# knife1.net
KiCad netlist of a schematic drawn in EAGLE
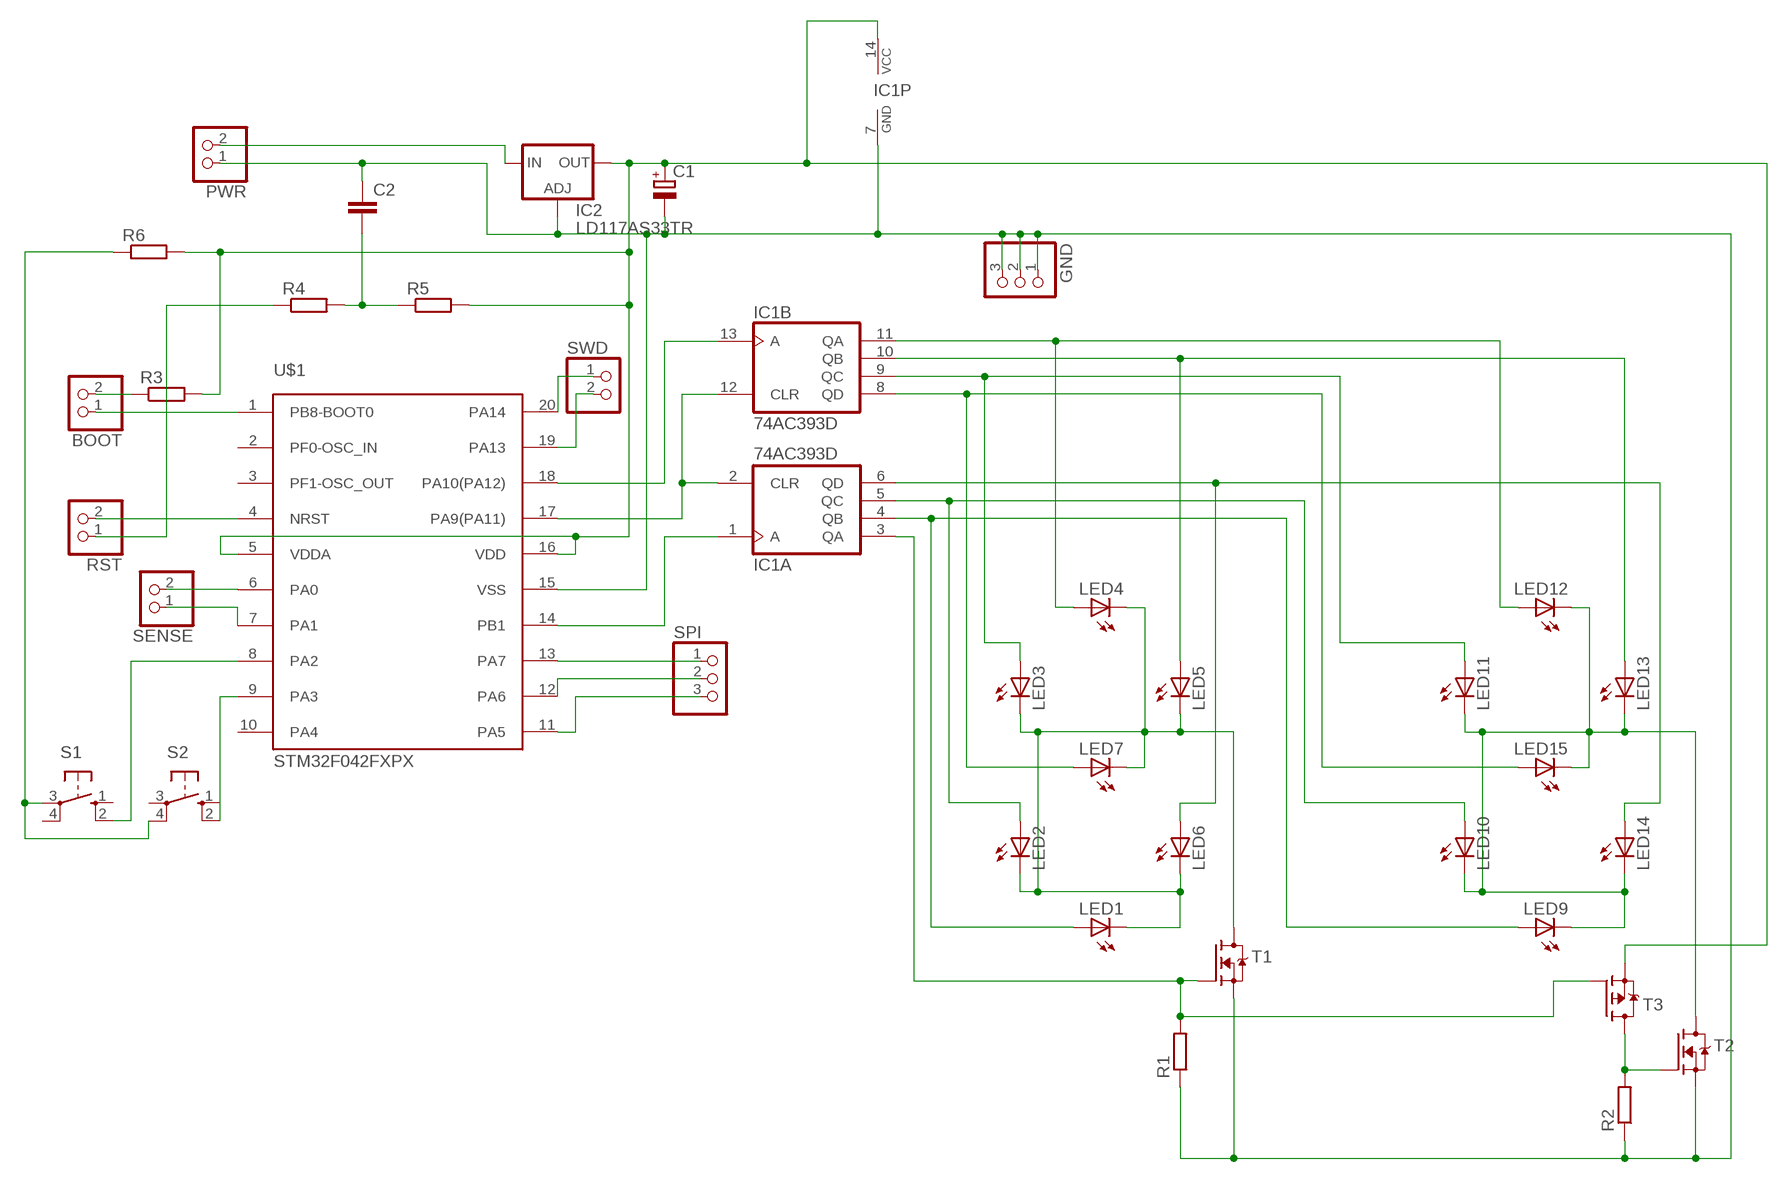
[diagram p0: schematic, sheet 1]

(export (version "E")
  (design (tool "Eeschema 10.0.6"))
  (components
    (comp (ref "BOOT")
      (value "PINHD-1X2")
      (footprint "eagle-import:1X02")
      (libsource (lib "eagle-import") (part "PINHD-1X2"))
    )
    (comp (ref "C1")
      (value "CPOL-EUSMCD")
      (footprint "eagle-import:SMC_D")
      (libsource (lib "eagle-import") (part "CPOL-EUSMCD"))
    )
    (comp (ref "C2")
      (value "C-EUC1206")
      (footprint "eagle-import:C1206")
      (libsource (lib "eagle-import") (part "C-EUC1206"))
    )
    (comp (ref "GND")
      (value "PINHD-1X3")
      (footprint "eagle-import:1X03")
      (libsource (lib "eagle-import") (part "PINHD-1X3"))
    )
    (comp (ref "IC1")
      (value "74AC393D")
      (footprint "eagle-import:SO14")
      (libsource (lib "eagle-import") (part "74393DAC"))
    )
    (comp (ref "IC2")
      (value "LD117AS33TR")
      (footprint "eagle-import:SOT223")
      (libsource (lib "eagle-import") (part "LD117A?S33TR"))
    )
    (comp (ref "LED1")
      (value "LEDSQR2X5")
      (footprint "eagle-import:LED2X5")
      (libsource (lib "eagle-import") (part "LEDSQR2X5"))
    )
    (comp (ref "LED2")
      (value "LEDSQR2X5")
      (footprint "eagle-import:LED2X5")
      (libsource (lib "eagle-import") (part "LEDSQR2X5"))
    )
    (comp (ref "LED3")
      (value "LEDSQR2X5")
      (footprint "eagle-import:LED2X5")
      (libsource (lib "eagle-import") (part "LEDSQR2X5"))
    )
    (comp (ref "LED4")
      (value "LEDSQR2X5")
      (footprint "eagle-import:LED2X5")
      (libsource (lib "eagle-import") (part "LEDSQR2X5"))
    )
    (comp (ref "LED5")
      (value "LEDSQR2X5")
      (footprint "eagle-import:LED2X5")
      (libsource (lib "eagle-import") (part "LEDSQR2X5"))
    )
    (comp (ref "LED6")
      (value "LEDSQR2X5")
      (footprint "eagle-import:LED2X5")
      (libsource (lib "eagle-import") (part "LEDSQR2X5"))
    )
    (comp (ref "LED7")
      (value "LEDSQR2X5")
      (footprint "eagle-import:LED2X5")
      (libsource (lib "eagle-import") (part "LEDSQR2X5"))
    )
    (comp (ref "LED9")
      (value "LEDSQR2X5")
      (footprint "eagle-import:LED2X5")
      (libsource (lib "eagle-import") (part "LEDSQR2X5"))
    )
    (comp (ref "LED10")
      (value "LEDSQR2X5")
      (footprint "eagle-import:LED2X5")
      (libsource (lib "eagle-import") (part "LEDSQR2X5"))
    )
    (comp (ref "LED11")
      (value "LEDSQR2X5")
      (footprint "eagle-import:LED2X5")
      (libsource (lib "eagle-import") (part "LEDSQR2X5"))
    )
    (comp (ref "LED12")
      (value "LEDSQR2X5")
      (footprint "eagle-import:LED2X5")
      (libsource (lib "eagle-import") (part "LEDSQR2X5"))
    )
    (comp (ref "LED13")
      (value "LEDSQR2X5")
      (footprint "eagle-import:LED2X5")
      (libsource (lib "eagle-import") (part "LEDSQR2X5"))
    )
    (comp (ref "LED14")
      (value "LEDSQR2X5")
      (footprint "eagle-import:LED2X5")
      (libsource (lib "eagle-import") (part "LEDSQR2X5"))
    )
    (comp (ref "LED15")
      (value "LEDSQR2X5")
      (footprint "eagle-import:LED2X5")
      (libsource (lib "eagle-import") (part "LEDSQR2X5"))
    )
    (comp (ref "PWR")
      (value "PINHD-1X2")
      (footprint "eagle-import:1X02")
      (libsource (lib "eagle-import") (part "PINHD-1X2"))
    )
    (comp (ref "R1")
      (value "R-EU_M1206")
      (footprint "eagle-import:M1206")
      (libsource (lib "eagle-import") (part "R-EU_M1206"))
    )
    (comp (ref "R2")
      (value "R-EU_M1206")
      (footprint "eagle-import:M1206")
      (libsource (lib "eagle-import") (part "R-EU_M1206"))
    )
    (comp (ref "R3")
      (value "R-EU_M1206")
      (footprint "eagle-import:M1206")
      (libsource (lib "eagle-import") (part "R-EU_M1206"))
    )
    (comp (ref "R4")
      (value "R-EU_M1206")
      (footprint "eagle-import:M1206")
      (libsource (lib "eagle-import") (part "R-EU_M1206"))
    )
    (comp (ref "R5")
      (value "R-EU_M1206")
      (footprint "eagle-import:M1206")
      (libsource (lib "eagle-import") (part "R-EU_M1206"))
    )
    (comp (ref "R6")
      (value "R-EU_M1206")
      (footprint "eagle-import:M1206")
      (libsource (lib "eagle-import") (part "R-EU_M1206"))
    )
    (comp (ref "RST")
      (value "PINHD-1X2")
      (footprint "eagle-import:1X02")
      (libsource (lib "eagle-import") (part "PINHD-1X2"))
    )
    (comp (ref "S1")
      (value "10-XX")
      (footprint "eagle-import:B3F-10XX")
      (fields (field (name "MPN") "B3F-1000"))
      (libsource (lib "eagle-import") (part "10-XX"))
    )
    (comp (ref "S2")
      (value "10-XX")
      (footprint "eagle-import:B3F-10XX")
      (fields (field (name "MPN") "B3F-1000"))
      (libsource (lib "eagle-import") (part "10-XX"))
    )
    (comp (ref "SENSE")
      (value "PINHD-1X2")
      (footprint "eagle-import:1X02")
      (libsource (lib "eagle-import") (part "PINHD-1X2"))
    )
    (comp (ref "SPI")
      (value "PINHD-1X3")
      (footprint "eagle-import:1X03")
      (libsource (lib "eagle-import") (part "PINHD-1X3"))
    )
    (comp (ref "SWD")
      (value "PINHD-1X2")
      (footprint "eagle-import:1X02")
      (libsource (lib "eagle-import") (part "PINHD-1X2"))
    )
    (comp (ref "T1")
      (value "MOSFET-N-SOT23")
      (footprint "eagle-import:SOT23")
      (libsource (lib "eagle-import") (part "MOSFET-N-SOT23"))
    )
    (comp (ref "T2")
      (value "MOSFET-N-SOT23")
      (footprint "eagle-import:SOT23")
      (libsource (lib "eagle-import") (part "MOSFET-N-SOT23"))
    )
    (comp (ref "T3")
      (value "MOSFET-P-SOT23")
      (footprint "eagle-import:SOT23")
      (libsource (lib "eagle-import") (part "MOSFET-P-SOT23"))
    )
    (comp (ref "U$1")
      (value "STM32F042FXPX")
      (footprint "eagle-import:TSSOP20")
      (libsource (lib "eagle-import") (part "STM32F042FXPX"))
    )
  )
  (nets
    (net (code "1") (name "Net-(BOOT-Pad2)") (class "Default")
      (node (ref "BOOT") (pin "2") (pinfunction "2_2") (pintype "passive"))
      (node (ref "R3") (pin "1") (pinfunction "1_1") (pintype "passive"))
    )
    (net (code "2") (name "Net-(C2-Pad2)") (class "Default")
      (node (ref "C2") (pin "2") (pinfunction "2_2") (pintype "passive"))
      (node (ref "R4") (pin "2") (pinfunction "2_2") (pintype "passive"))
      (node (ref "R5") (pin "1") (pinfunction "1_1") (pintype "passive"))
    )
    (net (code "3") (name "Net-(IC1A-A)") (class "Default")
      (node (ref "IC1") (pin "1") (pinfunction "A_1") (pintype "input"))
      (node (ref "U$1") (pin "14") (pinfunction "PB1_14") (pintype "bidirectional"))
    )
    (net (code "4") (name "Net-(IC1A-CLR)") (class "Default")
      (node (ref "IC1") (pin "12") (pinfunction "CLR_12") (pintype "input"))
      (node (ref "IC1") (pin "2") (pinfunction "CLR_2") (pintype "input"))
      (node (ref "U$1") (pin "17") (pinfunction "PA9(PA11)_17") (pintype "bidirectional"))
    )
    (net (code "5") (name "Net-(IC1A-QA)") (class "Default")
      (node (ref "IC1") (pin "3") (pinfunction "QA_3") (pintype "output"))
      (node (ref "R1") (pin "2") (pinfunction "2_2") (pintype "passive"))
      (node (ref "T1") (pin "1") (pinfunction "G_1") (pintype "passive"))
      (node (ref "T3") (pin "1") (pinfunction "G_1") (pintype "passive"))
    )
    (net (code "6") (name "Net-(IC1A-QB)") (class "Default")
      (node (ref "IC1") (pin "4") (pinfunction "QB_4") (pintype "output"))
      (node (ref "LED1") (pin "A") (pinfunction "A_A") (pintype "passive"))
      (node (ref "LED9") (pin "A") (pinfunction "A_A") (pintype "passive"))
    )
    (net (code "7") (name "Net-(IC1A-QC)") (class "Default")
      (node (ref "IC1") (pin "5") (pinfunction "QC_5") (pintype "output"))
      (node (ref "LED10") (pin "A") (pinfunction "A_A") (pintype "passive"))
      (node (ref "LED2") (pin "A") (pinfunction "A_A") (pintype "passive"))
    )
    (net (code "8") (name "Net-(IC1A-QD)") (class "Default")
      (node (ref "IC1") (pin "6") (pinfunction "QD_6") (pintype "output"))
      (node (ref "LED14") (pin "A") (pinfunction "A_A") (pintype "passive"))
      (node (ref "LED6") (pin "A") (pinfunction "A_A") (pintype "passive"))
    )
    (net (code "9") (name "Net-(IC1B-A)") (class "Default")
      (node (ref "IC1") (pin "13") (pinfunction "A_13") (pintype "input"))
      (node (ref "U$1") (pin "18") (pinfunction "PA10(PA12)_18") (pintype "bidirectional"))
    )
    (net (code "10") (name "Net-(IC1B-QA)") (class "Default")
      (node (ref "IC1") (pin "11") (pinfunction "QA_11") (pintype "output"))
      (node (ref "LED12") (pin "A") (pinfunction "A_A") (pintype "passive"))
      (node (ref "LED4") (pin "A") (pinfunction "A_A") (pintype "passive"))
    )
    (net (code "11") (name "Net-(IC1B-QB)") (class "Default")
      (node (ref "IC1") (pin "10") (pinfunction "QB_10") (pintype "output"))
      (node (ref "LED13") (pin "A") (pinfunction "A_A") (pintype "passive"))
      (node (ref "LED5") (pin "A") (pinfunction "A_A") (pintype "passive"))
    )
    (net (code "12") (name "Net-(IC1B-QC)") (class "Default")
      (node (ref "IC1") (pin "9") (pinfunction "QC_9") (pintype "output"))
      (node (ref "LED11") (pin "A") (pinfunction "A_A") (pintype "passive"))
      (node (ref "LED3") (pin "A") (pinfunction "A_A") (pintype "passive"))
    )
    (net (code "13") (name "Net-(IC1B-QD)") (class "Default")
      (node (ref "IC1") (pin "8") (pinfunction "QD_8") (pintype "output"))
      (node (ref "LED15") (pin "A") (pinfunction "A_A") (pintype "passive"))
      (node (ref "LED7") (pin "A") (pinfunction "A_A") (pintype "passive"))
    )
    (net (code "14") (name "Net-(IC1C-GND)") (class "Default")
      (node (ref "C1") (pin "-") (pinfunction "-_-") (pintype "passive"))
      (node (ref "C2") (pin "1") (pinfunction "1_1") (pintype "passive"))
      (node (ref "GND") (pin "1") (pinfunction "1_1") (pintype "passive"))
      (node (ref "GND") (pin "2") (pinfunction "2_2") (pintype "passive"))
      (node (ref "GND") (pin "3") (pinfunction "3_3") (pintype "passive"))
      (node (ref "IC1") (pin "7") (pinfunction "GND_7") (pintype "power_in"))
      (node (ref "IC2") (pin "1") (pinfunction "ADJ_1") (pintype "input"))
      (node (ref "PWR") (pin "1") (pinfunction "1_1") (pintype "passive"))
      (node (ref "R1") (pin "1") (pinfunction "1_1") (pintype "passive"))
      (node (ref "R2") (pin "1") (pinfunction "1_1") (pintype "passive"))
      (node (ref "T1") (pin "2") (pinfunction "S_2") (pintype "passive"))
      (node (ref "T2") (pin "2") (pinfunction "S_2") (pintype "passive"))
      (node (ref "U$1") (pin "15") (pinfunction "VSS_15") (pintype "bidirectional"))
    )
    (net (code "15") (name "Net-(IC1C-VCC)") (class "Default")
      (node (ref "C1") (pin "+") (pinfunction "+_+") (pintype "passive"))
      (node (ref "IC1") (pin "14") (pinfunction "VCC_14") (pintype "power_in"))
      (node (ref "IC2") (pin "4") (pinfunction "OUT_4") (pintype "passive"))
      (node (ref "R3") (pin "2") (pinfunction "2_2") (pintype "passive"))
      (node (ref "R5") (pin "2") (pinfunction "2_2") (pintype "passive"))
      (node (ref "R6") (pin "2") (pinfunction "2_2") (pintype "passive"))
      (node (ref "T3") (pin "2") (pinfunction "S_2") (pintype "passive"))
      (node (ref "U$1") (pin "16") (pinfunction "VDD_16") (pintype "bidirectional"))
      (node (ref "U$1") (pin "5") (pinfunction "VDDA_5") (pintype "bidirectional"))
    )
    (net (code "16") (name "Net-(IC2-IN)") (class "Default")
      (node (ref "IC2") (pin "3") (pinfunction "IN_3") (pintype "input"))
      (node (ref "PWR") (pin "2") (pinfunction "2_2") (pintype "passive"))
    )
    (net (code "17") (name "Net-(LED1-C)") (class "Default")
      (node (ref "LED1") (pin "K") (pinfunction "C_K") (pintype "passive"))
      (node (ref "LED2") (pin "K") (pinfunction "C_K") (pintype "passive"))
      (node (ref "LED3") (pin "K") (pinfunction "C_K") (pintype "passive"))
      (node (ref "LED4") (pin "K") (pinfunction "C_K") (pintype "passive"))
      (node (ref "LED5") (pin "K") (pinfunction "C_K") (pintype "passive"))
      (node (ref "LED6") (pin "K") (pinfunction "C_K") (pintype "passive"))
      (node (ref "LED7") (pin "K") (pinfunction "C_K") (pintype "passive"))
      (node (ref "T1") (pin "3") (pinfunction "D_3") (pintype "passive"))
    )
    (net (code "18") (name "Net-(LED10-C)") (class "Default")
      (node (ref "LED10") (pin "K") (pinfunction "C_K") (pintype "passive"))
      (node (ref "LED11") (pin "K") (pinfunction "C_K") (pintype "passive"))
      (node (ref "LED12") (pin "K") (pinfunction "C_K") (pintype "passive"))
      (node (ref "LED13") (pin "K") (pinfunction "C_K") (pintype "passive"))
      (node (ref "LED14") (pin "K") (pinfunction "C_K") (pintype "passive"))
      (node (ref "LED15") (pin "K") (pinfunction "C_K") (pintype "passive"))
      (node (ref "LED9") (pin "K") (pinfunction "C_K") (pintype "passive"))
      (node (ref "T2") (pin "3") (pinfunction "D_3") (pintype "passive"))
    )
    (net (code "19") (name "Net-(R4-Pad1)") (class "Default")
      (node (ref "R4") (pin "1") (pinfunction "1_1") (pintype "passive"))
      (node (ref "RST") (pin "1") (pinfunction "1_1") (pintype "passive"))
    )
    (net (code "20") (name "Net-(S1-P)") (class "Default")
      (node (ref "R6") (pin "1") (pinfunction "1_1") (pintype "passive"))
      (node (ref "S1") (pin "3") (pinfunction "P_3") (pintype "passive"))
      (node (ref "S2") (pin "4") (pinfunction "P1_4") (pintype "passive"))
    )
    (net (code "21") (name "Net-(S1-S1)") (class "Default")
      (node (ref "S1") (pin "2") (pinfunction "S1_2") (pintype "passive"))
      (node (ref "U$1") (pin "8") (pinfunction "PA2_8") (pintype "bidirectional"))
    )
    (net (code "22") (name "Net-(S2-S1)") (class "Default")
      (node (ref "S2") (pin "2") (pinfunction "S1_2") (pintype "passive"))
      (node (ref "U$1") (pin "9") (pinfunction "PA3_9") (pintype "bidirectional"))
    )
    (net (code "23") (name "Net-(T2-G)") (class "Default")
      (node (ref "R2") (pin "2") (pinfunction "2_2") (pintype "passive"))
      (node (ref "T2") (pin "1") (pinfunction "G_1") (pintype "passive"))
      (node (ref "T3") (pin "3") (pinfunction "D_3") (pintype "passive"))
    )
    (net (code "24") (name "Net-(U$1-NRST)") (class "Default")
      (node (ref "RST") (pin "2") (pinfunction "2_2") (pintype "passive"))
      (node (ref "U$1") (pin "4") (pinfunction "NRST_4") (pintype "bidirectional"))
    )
    (net (code "25") (name "Net-(U$1-PA0)") (class "Default")
      (node (ref "SENSE") (pin "2") (pinfunction "2_2") (pintype "passive"))
      (node (ref "U$1") (pin "6") (pinfunction "PA0_6") (pintype "bidirectional"))
    )
    (net (code "26") (name "Net-(U$1-PA1)") (class "Default")
      (node (ref "SENSE") (pin "1") (pinfunction "1_1") (pintype "passive"))
      (node (ref "U$1") (pin "7") (pinfunction "PA1_7") (pintype "bidirectional"))
    )
    (net (code "27") (name "Net-(U$1-PA5)") (class "Default")
      (node (ref "SPI") (pin "3") (pinfunction "3_3") (pintype "passive"))
      (node (ref "U$1") (pin "11") (pinfunction "PA5_11") (pintype "bidirectional"))
    )
    (net (code "28") (name "Net-(U$1-PA6)") (class "Default")
      (node (ref "SPI") (pin "2") (pinfunction "2_2") (pintype "passive"))
      (node (ref "U$1") (pin "12") (pinfunction "PA6_12") (pintype "bidirectional"))
    )
    (net (code "29") (name "Net-(U$1-PA7)") (class "Default")
      (node (ref "SPI") (pin "1") (pinfunction "1_1") (pintype "passive"))
      (node (ref "U$1") (pin "13") (pinfunction "PA7_13") (pintype "bidirectional"))
    )
    (net (code "30") (name "Net-(U$1-PA13)") (class "Default")
      (node (ref "SWD") (pin "2") (pinfunction "2_2") (pintype "passive"))
      (node (ref "U$1") (pin "19") (pinfunction "PA13_19") (pintype "bidirectional"))
    )
    (net (code "31") (name "Net-(U$1-PA14)") (class "Default")
      (node (ref "SWD") (pin "1") (pinfunction "1_1") (pintype "passive"))
      (node (ref "U$1") (pin "20") (pinfunction "PA14_20") (pintype "bidirectional"))
    )
    (net (code "32") (name "Net-(U$1-PB8-BOOT0)") (class "Default")
      (node (ref "BOOT") (pin "1") (pinfunction "1_1") (pintype "passive"))
      (node (ref "U$1") (pin "1") (pinfunction "PB8-BOOT0_1") (pintype "bidirectional"))
    )
    (net (code "33") (name "unconnected-(S1-P1-Pad4)") (class "Default")
      (node (ref "S1") (pin "4") (pinfunction "P1_4") (pintype "passive"))
    )
    (net (code "34") (name "unconnected-(S1-S-Pad1)") (class "Default")
      (node (ref "S1") (pin "1") (pinfunction "S_1") (pintype "passive"))
    )
    (net (code "35") (name "unconnected-(S2-P-Pad3)") (class "Default")
      (node (ref "S2") (pin "3") (pinfunction "P_3") (pintype "passive"))
    )
    (net (code "36") (name "unconnected-(S2-S-Pad1)") (class "Default")
      (node (ref "S2") (pin "1") (pinfunction "S_1") (pintype "passive"))
    )
    (net (code "37") (name "unconnected-(U$1-PA4-Pad10)") (class "Default")
      (node (ref "U$1") (pin "10") (pinfunction "PA4_10") (pintype "bidirectional"))
    )
    (net (code "38") (name "unconnected-(U$1-PF0-OSC_IN-Pad2)") (class "Default")
      (node (ref "U$1") (pin "2") (pinfunction "PF0-OSC_IN_2") (pintype "bidirectional"))
    )
    (net (code "39") (name "unconnected-(U$1-PF1-OSC_OUT-Pad3)") (class "Default")
      (node (ref "U$1") (pin "3") (pinfunction "PF1-OSC_OUT_3") (pintype "bidirectional"))
    )
  )
)
